# main_board.net
KiCad netlist of a schematic drawn in EAGLE
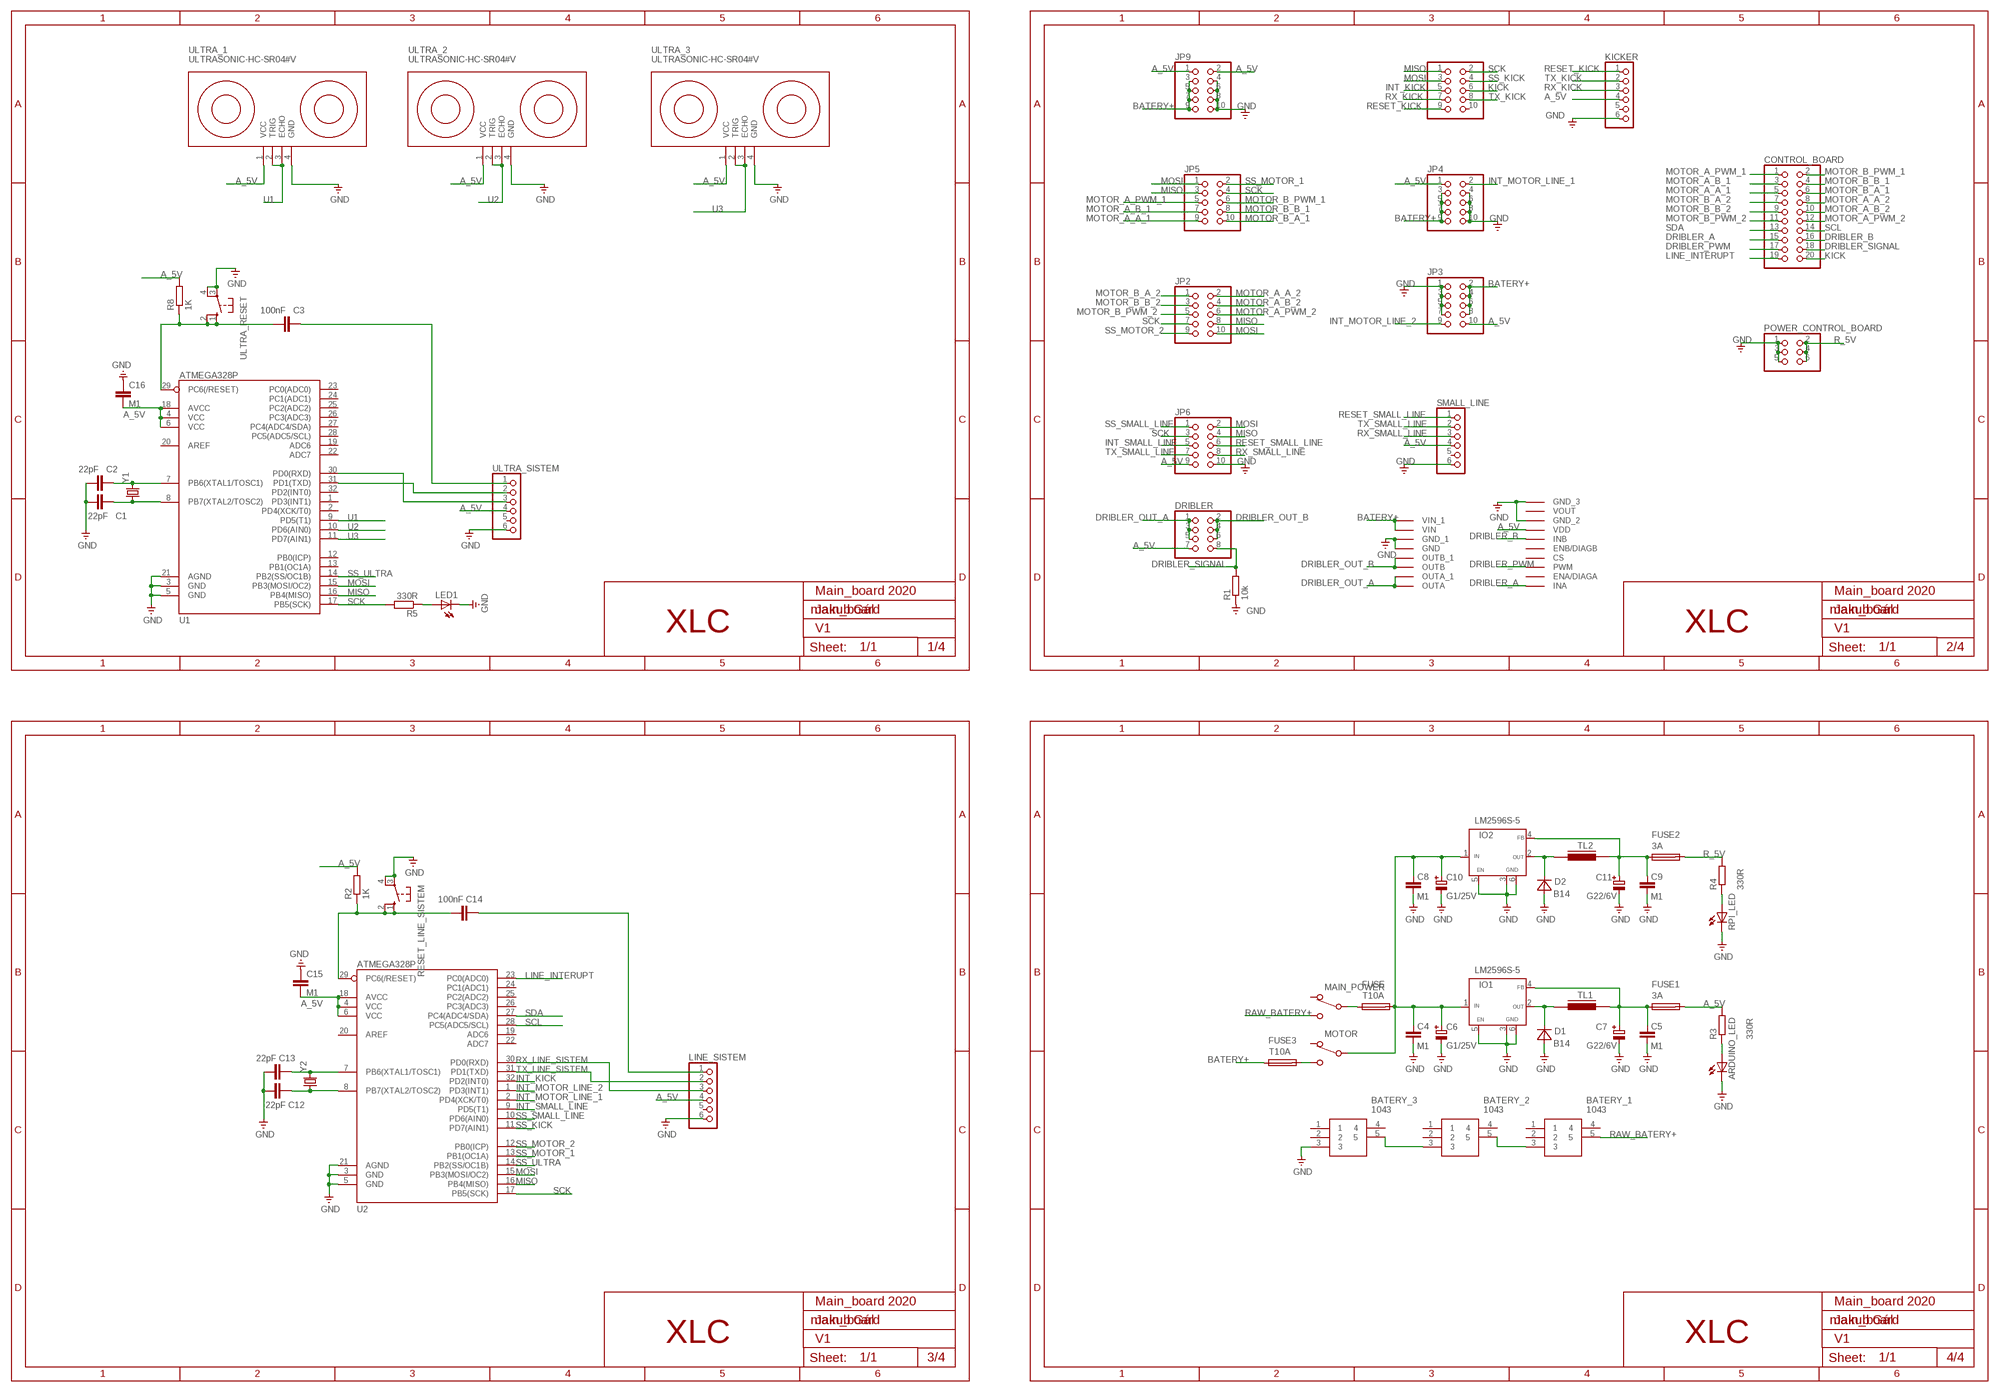
[diagram p0: schematic, sheet 1]

(export (version "E")
  (design (tool "Eeschema 10.0.6"))
  (components
    (comp (ref "ARDUINO_LED")
      (value "LEDCHIPLED_0603")
      (footprint "eagle-import:CHIPLED_0603")
      (libsource (lib "eagle-import") (part "LEDCHIPLED_0603"))
    )
    (comp (ref "BATERY_1")
      (value "1043")
      (footprint "eagle-import:1043")
      (fields (field (name "MOUSER_PART_NUMBER") "534-1043"))
      (libsource (lib "eagle-import") (part "1043"))
    )
    (comp (ref "BATERY_2")
      (value "1043")
      (footprint "eagle-import:1043")
      (fields (field (name "MOUSER_PART_NUMBER") "534-1043"))
      (libsource (lib "eagle-import") (part "1043"))
    )
    (comp (ref "BATERY_3")
      (value "1043")
      (footprint "eagle-import:1043")
      (fields (field (name "MOUSER_PART_NUMBER") "534-1043"))
      (libsource (lib "eagle-import") (part "1043"))
    )
    (comp (ref "C1")
      (value "22pF")
      (footprint "eagle-import:C0603")
      (libsource (lib "eagle-import") (part "C-EUC0603"))
    )
    (comp (ref "C2")
      (value "22pF")
      (footprint "eagle-import:C0603")
      (libsource (lib "eagle-import") (part "C-EUC0603"))
    )
    (comp (ref "C3")
      (value "100nF")
      (footprint "eagle-import:C0603")
      (libsource (lib "eagle-import") (part "C-EUC0603"))
    )
    (comp (ref "C4")
      (value "M1")
      (footprint "eagle-import:SMD-1206")
      (libsource (lib "eagle-import") (part "KOND-KERAM1206-SMD"))
    )
    (comp (ref "C5")
      (value "M1")
      (footprint "eagle-import:SMD-1206")
      (libsource (lib "eagle-import") (part "KOND-KERAM1206-SMD"))
    )
    (comp (ref "C6")
      (value "G1/25V")
      (footprint "eagle-import:SMD-ELE-D")
      (libsource (lib "eagle-import") (part "KOND-ELEKTD-SMD"))
    )
    (comp (ref "C7")
      (value "G22/6V")
      (footprint "eagle-import:SMD-ELE-D")
      (libsource (lib "eagle-import") (part "KOND-ELEKTD-SMD"))
    )
    (comp (ref "C8")
      (value "M1")
      (footprint "eagle-import:SMD-1206")
      (libsource (lib "eagle-import") (part "KOND-KERAM1206-SMD"))
    )
    (comp (ref "C9")
      (value "M1")
      (footprint "eagle-import:SMD-1206")
      (libsource (lib "eagle-import") (part "KOND-KERAM1206-SMD"))
    )
    (comp (ref "C10")
      (value "G1/25V")
      (footprint "eagle-import:SMD-ELE-D")
      (libsource (lib "eagle-import") (part "KOND-ELEKTD-SMD"))
    )
    (comp (ref "C11")
      (value "G22/6V")
      (footprint "eagle-import:SMD-ELE-D")
      (libsource (lib "eagle-import") (part "KOND-ELEKTD-SMD"))
    )
    (comp (ref "C12")
      (value "22pF")
      (footprint "eagle-import:C0603")
      (libsource (lib "eagle-import") (part "C-EUC0603"))
    )
    (comp (ref "C13")
      (value "22pF")
      (footprint "eagle-import:C0603")
      (libsource (lib "eagle-import") (part "C-EUC0603"))
    )
    (comp (ref "C14")
      (value "100nF")
      (footprint "eagle-import:C0603")
      (libsource (lib "eagle-import") (part "C-EUC0603"))
    )
    (comp (ref "C15")
      (value "M1")
      (footprint "eagle-import:C0603")
      (libsource (lib "eagle-import") (part "rcl_334_C-EUC0603"))
    )
    (comp (ref "C16")
      (value "M1")
      (footprint "eagle-import:C0603")
      (libsource (lib "eagle-import") (part "rcl_334_C-EUC0603"))
    )
    (comp (ref "CONTROL_BOARD")
      (value "PINHD-2X10_2.54-SMD")
      (footprint "eagle-import:2X10SMD")
      (libsource (lib "eagle-import") (part "PINHD-2X10_2.54-SMD"))
    )
    (comp (ref "D1")
      (value "B14")
      (footprint "eagle-import:D-3,6X5,5")
      (libsource (lib "eagle-import") (part "DIODASMD-3,6X5,5"))
    )
    (comp (ref "D2")
      (value "B14")
      (footprint "eagle-import:D-3,6X5,5")
      (libsource (lib "eagle-import") (part "DIODASMD-3,6X5,5"))
    )
    (comp (ref "DRIBLER")
      (value "PINHD-2X4_2.54-SMD")
      (footprint "eagle-import:2X04SMD")
      (libsource (lib "eagle-import") (part "PINHD-2X4_2.54-SMD"))
    )
    (comp (ref "FUSE")
      (value "T10A")
      (footprint "eagle-import:SH22,5A")
      (libsource (lib "eagle-import") (part "POISTKA2A"))
    )
    (comp (ref "FUSE1")
      (value "3A")
      (footprint "eagle-import:SH22,5A")
      (libsource (lib "eagle-import") (part "POISTKA2A"))
    )
    (comp (ref "FUSE2")
      (value "3A")
      (footprint "eagle-import:SH22,5A")
      (libsource (lib "eagle-import") (part "POISTKA2A"))
    )
    (comp (ref "FUSE3")
      (value "T10A")
      (footprint "eagle-import:SH22,5A")
      (libsource (lib "eagle-import") (part "POISTKA2A"))
    )
    (comp (ref "IO1")
      (value "LM2596S-5")
      (footprint "eagle-import:TO263-5")
      (libsource (lib "eagle-import") (part "LM2596S"))
    )
    (comp (ref "IO2")
      (value "LM2596S-5")
      (footprint "eagle-import:TO263-5")
      (libsource (lib "eagle-import") (part "LM2596S"))
    )
    (comp (ref "JP2")
      (value "PINHD-2X5_2.54-SMD")
      (footprint "eagle-import:2X05SMD")
      (libsource (lib "eagle-import") (part "PINHD-2X5_2.54-SMD"))
    )
    (comp (ref "JP3")
      (value "PINHD-2X5_2.54-SMD")
      (footprint "eagle-import:2X05SMD")
      (libsource (lib "eagle-import") (part "PINHD-2X5_2.54-SMD"))
    )
    (comp (ref "JP4")
      (value "PINHD-2X5_2.54-SMD")
      (footprint "eagle-import:2X05SMD")
      (libsource (lib "eagle-import") (part "PINHD-2X5_2.54-SMD"))
    )
    (comp (ref "JP5")
      (value "PINHD-2X5_2.54-SMD")
      (footprint "eagle-import:2X05SMD")
      (libsource (lib "eagle-import") (part "PINHD-2X5_2.54-SMD"))
    )
    (comp (ref "JP6")
      (value "PINHD-2X5_2.54-SMD")
      (footprint "eagle-import:2X05SMD")
      (libsource (lib "eagle-import") (part "PINHD-2X5_2.54-SMD"))
    )
    (comp (ref "JP8")
      (value "PINHD-2X5_2.54-SMD")
      (footprint "eagle-import:2X05SMD")
      (libsource (lib "eagle-import") (part "PINHD-2X5_2.54-SMD"))
    )
    (comp (ref "JP9")
      (value "PINHD-2X5_2.54-SMD")
      (footprint "eagle-import:2X05SMD")
      (libsource (lib "eagle-import") (part "PINHD-2X5_2.54-SMD"))
    )
    (comp (ref "KICKER")
      (value "PINHD-1X6")
      (footprint "eagle-import:1X06")
      (libsource (lib "eagle-import") (part "PINHD-1X6"))
    )
    (comp (ref "LED1")
      (value "LEDCHIPLED_0603")
      (footprint "eagle-import:CHIPLED_0603")
      (libsource (lib "eagle-import") (part "LEDCHIPLED_0603"))
    )
    (comp (ref "LINE_SISTEM")
      (value "PINHD-1X6")
      (footprint "eagle-import:1X06")
      (libsource (lib "eagle-import") (part "PINHD-1X6"))
    )
    (comp (ref "MAIN_POWER")
      (value "PREP-1PB")
      (footprint "eagle-import:P-B069B")
      (libsource (lib "eagle-import") (part "PREP-1PB"))
    )
    (comp (ref "MOTOR")
      (value "PREP-1PB")
      (footprint "eagle-import:P-B069B")
      (libsource (lib "eagle-import") (part "PREP-1PB"))
    )
    (comp (ref "POWER_CONTROL_BOARD")
      (value "PINHD-2X3_2.54-SMD")
      (footprint "eagle-import:2X03SMD")
      (libsource (lib "eagle-import") (part "PINHD-2X3_2.54-SMD"))
    )
    (comp (ref "R1")
      (value "10k")
      (footprint "eagle-import:R0603")
      (libsource (lib "eagle-import") (part "R-EU_R0603"))
    )
    (comp (ref "R2")
      (value "1K")
      (footprint "eagle-import:R0603")
      (libsource (lib "eagle-import") (part "R-EU_R0603"))
    )
    (comp (ref "R3")
      (value "330R")
      (footprint "eagle-import:R0603")
      (libsource (lib "eagle-import") (part "R-EU_R0603"))
    )
    (comp (ref "R4")
      (value "330R")
      (footprint "eagle-import:R0603")
      (libsource (lib "eagle-import") (part "R-EU_R0603"))
    )
    (comp (ref "R5")
      (value "330R")
      (footprint "eagle-import:R0603")
      (libsource (lib "eagle-import") (part "R-EU_R0603"))
    )
    (comp (ref "R8")
      (value "1K")
      (footprint "eagle-import:R0603")
      (libsource (lib "eagle-import") (part "R-EU_R0603"))
    )
    (comp (ref "RESET_LINE_SISTEM")
      (value "10-XX")
      (footprint "eagle-import:B3F-10XX")
      (fields (field (name "MPN") "B3F-1000"))
      (libsource (lib "eagle-import") (part "10-XX"))
    )
    (comp (ref "RPI_LED")
      (value "LEDCHIPLED_0603")
      (footprint "eagle-import:CHIPLED_0603")
      (libsource (lib "eagle-import") (part "LEDCHIPLED_0603"))
    )
    (comp (ref "SMALL_LINE")
      (value "PINHD-1X6")
      (footprint "eagle-import:1X06")
      (libsource (lib "eagle-import") (part "PINHD-1X6"))
    )
    (comp (ref "TL1")
      (value "INDUK-TLSMD1")
      (footprint "eagle-import:INDUK-TL")
      (libsource (lib "eagle-import") (part "INDUK-TLSMD1"))
    )
    (comp (ref "TL2")
      (value "INDUK-TLSMD1")
      (footprint "eagle-import:INDUK-TL")
      (libsource (lib "eagle-import") (part "INDUK-TLSMD1"))
    )
    (comp (ref "U$4")
      (value "MOTOR_DRIVER")
      (footprint "eagle-import:MOTOR_DRIVER")
      (libsource (lib "eagle-import") (part "MOTOR_DRIVER"))
    )
    (comp (ref "U1")
      (value "ATMEGA328P")
      (footprint "eagle-import:TQFP32-08")
      (libsource (lib "eagle-import") (part "ATMEGA328_SMT"))
    )
    (comp (ref "U2")
      (value "ATMEGA328P")
      (footprint "eagle-import:TQFP32-08")
      (libsource (lib "eagle-import") (part "ATMEGA328_SMT"))
    )
    (comp (ref "ULTRA_1")
      (value "ULTRASONIC-HC-SR04#V")
      (footprint "eagle-import:ULTRASONIC-HC-SR04#V")
      (libsource (lib "eagle-import") (part "ULTRASONIC-HC-SR04#V"))
    )
    (comp (ref "ULTRA_2")
      (value "ULTRASONIC-HC-SR04#V")
      (footprint "eagle-import:ULTRASONIC-HC-SR04#V")
      (libsource (lib "eagle-import") (part "ULTRASONIC-HC-SR04#V"))
    )
    (comp (ref "ULTRA_3")
      (value "ULTRASONIC-HC-SR04#V")
      (footprint "eagle-import:ULTRASONIC-HC-SR04#V")
      (libsource (lib "eagle-import") (part "ULTRASONIC-HC-SR04#V"))
    )
    (comp (ref "ULTRA_RESET")
      (value "10-XX")
      (footprint "eagle-import:B3F-10XX")
      (fields (field (name "MPN") "B3F-1000"))
      (libsource (lib "eagle-import") (part "10-XX"))
    )
    (comp (ref "ULTRA_SISTEM")
      (value "PINHD-1X6")
      (footprint "eagle-import:1X06")
      (libsource (lib "eagle-import") (part "PINHD-1X6"))
    )
    (comp (ref "Y1")
      (value "CRYSTALHC49US")
      (footprint "eagle-import:HC49US")
      (libsource (lib "eagle-import") (part "CRYSTALHC49US"))
    )
    (comp (ref "Y2")
      (value "CRYSTALHC49US")
      (footprint "eagle-import:HC49US")
      (libsource (lib "eagle-import") (part "CRYSTALHC49US"))
    )
  )
  (nets
    (net (code "1") (name "/A_5V") (class "Default")
      (node (ref "C15") (pin "2") (pinfunction "2_2") (pintype "passive"))
      (node (ref "C16") (pin "2") (pinfunction "2_2") (pintype "passive"))
      (node (ref "DRIBLER") (pin "7") (pinfunction "7_7") (pintype "passive"))
      (node (ref "FUSE1") (pin "2") (pinfunction "2_2") (pintype "passive"))
      (node (ref "JP3") (pin "10") (pinfunction "10_10") (pintype "passive"))
      (node (ref "JP4") (pin "1") (pinfunction "1_1") (pintype "passive"))
      (node (ref "JP6") (pin "9") (pinfunction "9_9") (pintype "passive"))
      (node (ref "JP9") (pin "1") (pinfunction "1_1") (pintype "passive"))
      (node (ref "JP9") (pin "2") (pinfunction "2_2") (pintype "passive"))
      (node (ref "KICKER") (pin "4") (pinfunction "4_4") (pintype "passive"))
      (node (ref "LINE_SISTEM") (pin "4") (pinfunction "4_4") (pintype "passive"))
      (node (ref "R2") (pin "2") (pinfunction "2_2") (pintype "passive"))
      (node (ref "R3") (pin "2") (pinfunction "2_2") (pintype "passive"))
      (node (ref "R8") (pin "2") (pinfunction "2_2") (pintype "passive"))
      (node (ref "SMALL_LINE") (pin "4") (pinfunction "4_4") (pintype "passive"))
      (node (ref "U$4") (pin "VDD") (pinfunction "VDD_VDD") (pintype "bidirectional"))
      (node (ref "U1") (pin "18") (pinfunction "AVCC_18") (pintype "bidirectional"))
      (node (ref "U1") (pin "4") (pinfunction "VCC_4") (pintype "bidirectional"))
      (node (ref "U1") (pin "6") (pinfunction "VCC_6") (pintype "bidirectional"))
      (node (ref "U2") (pin "18") (pinfunction "AVCC_18") (pintype "bidirectional"))
      (node (ref "U2") (pin "4") (pinfunction "VCC_4") (pintype "bidirectional"))
      (node (ref "U2") (pin "6") (pinfunction "VCC_6") (pintype "bidirectional"))
      (node (ref "ULTRA_1") (pin "1") (pinfunction "VCC_1") (pintype "power_in"))
      (node (ref "ULTRA_2") (pin "1") (pinfunction "VCC_1") (pintype "power_in"))
      (node (ref "ULTRA_3") (pin "1") (pinfunction "VCC_1") (pintype "power_in"))
      (node (ref "ULTRA_SISTEM") (pin "4") (pinfunction "4_4") (pintype "passive"))
    )
    (net (code "2") (name "/BATERY+") (class "Default")
      (node (ref "FUSE3") (pin "1") (pinfunction "1_1") (pintype "passive"))
      (node (ref "JP3") (pin "2") (pinfunction "2_2") (pintype "passive"))
      (node (ref "JP3") (pin "4") (pinfunction "4_4") (pintype "passive"))
      (node (ref "JP3") (pin "6") (pinfunction "6_6") (pintype "passive"))
      (node (ref "JP3") (pin "8") (pinfunction "8_8") (pintype "passive"))
      (node (ref "JP4") (pin "3") (pinfunction "3_3") (pintype "passive"))
      (node (ref "JP4") (pin "5") (pinfunction "5_5") (pintype "passive"))
      (node (ref "JP4") (pin "7") (pinfunction "7_7") (pintype "passive"))
      (node (ref "JP4") (pin "9") (pinfunction "9_9") (pintype "passive"))
      (node (ref "JP9") (pin "3") (pinfunction "3_3") (pintype "passive"))
      (node (ref "JP9") (pin "5") (pinfunction "5_5") (pintype "passive"))
      (node (ref "JP9") (pin "7") (pinfunction "7_7") (pintype "passive"))
      (node (ref "JP9") (pin "9") (pinfunction "9_9") (pintype "passive"))
      (node (ref "U$4") (pin "VIN") (pinfunction "VIN_VIN") (pintype "bidirectional"))
      (node (ref "U$4") (pin "VIN_1") (pinfunction "VIN_1_VIN_1") (pintype "bidirectional"))
    )
    (net (code "3") (name "/DRIBLER_A") (class "Default")
      (node (ref "CONTROL_BOARD") (pin "15") (pinfunction "15_15") (pintype "passive"))
      (node (ref "U$4") (pin "INA") (pinfunction "INA_INA") (pintype "bidirectional"))
    )
    (net (code "4") (name "/DRIBLER_B") (class "Default")
      (node (ref "CONTROL_BOARD") (pin "16") (pinfunction "16_16") (pintype "passive"))
      (node (ref "U$4") (pin "INB") (pinfunction "INB_INB") (pintype "bidirectional"))
    )
    (net (code "5") (name "/DRIBLER_OUT_A") (class "Default")
      (node (ref "DRIBLER") (pin "1") (pinfunction "1_1") (pintype "passive"))
      (node (ref "DRIBLER") (pin "3") (pinfunction "3_3") (pintype "passive"))
      (node (ref "DRIBLER") (pin "5") (pinfunction "5_5") (pintype "passive"))
      (node (ref "U$4") (pin "OUTA") (pinfunction "OUTA_OUTA") (pintype "bidirectional"))
      (node (ref "U$4") (pin "OUTA_1") (pinfunction "OUTA_1_OUTA_1") (pintype "bidirectional"))
    )
    (net (code "6") (name "/DRIBLER_OUT_B") (class "Default")
      (node (ref "DRIBLER") (pin "2") (pinfunction "2_2") (pintype "passive"))
      (node (ref "DRIBLER") (pin "4") (pinfunction "4_4") (pintype "passive"))
      (node (ref "DRIBLER") (pin "6") (pinfunction "6_6") (pintype "passive"))
      (node (ref "U$4") (pin "OUTB") (pinfunction "OUTB_OUTB") (pintype "bidirectional"))
      (node (ref "U$4") (pin "OUTB_1") (pinfunction "OUTB_1_OUTB_1") (pintype "bidirectional"))
    )
    (net (code "7") (name "/DRIBLER_PWM") (class "Default")
      (node (ref "CONTROL_BOARD") (pin "17") (pinfunction "17_17") (pintype "passive"))
      (node (ref "U$4") (pin "PWM") (pinfunction "PWM_PWM") (pintype "bidirectional"))
    )
    (net (code "8") (name "/DRIBLER_SIGNAL") (class "Default")
      (node (ref "CONTROL_BOARD") (pin "18") (pinfunction "18_18") (pintype "passive"))
      (node (ref "DRIBLER") (pin "8") (pinfunction "8_8") (pintype "passive"))
      (node (ref "R1") (pin "2") (pinfunction "2_2") (pintype "passive"))
    )
    (net (code "9") (name "/INT_KICK") (class "Default")
      (node (ref "JP8") (pin "5") (pinfunction "5_5") (pintype "passive"))
      (node (ref "U2") (pin "32") (pinfunction "PD2(INT0)_32") (pintype "bidirectional"))
    )
    (net (code "10") (name "/INT_MOTOR_LINE_1") (class "Default")
      (node (ref "JP4") (pin "2") (pinfunction "2_2") (pintype "passive"))
      (node (ref "U2") (pin "2") (pinfunction "PD4(XCK/T0)_2") (pintype "bidirectional"))
    )
    (net (code "11") (name "/INT_MOTOR_LINE_2") (class "Default")
      (node (ref "JP3") (pin "9") (pinfunction "9_9") (pintype "passive"))
      (node (ref "U2") (pin "1") (pinfunction "PD3(INT1)_1") (pintype "bidirectional"))
    )
    (net (code "12") (name "/INT_SMALL_LINE") (class "Default")
      (node (ref "JP6") (pin "5") (pinfunction "5_5") (pintype "passive"))
      (node (ref "U2") (pin "9") (pinfunction "PD5(T1)_9") (pintype "bidirectional"))
    )
    (net (code "13") (name "/KICK") (class "Default")
      (node (ref "CONTROL_BOARD") (pin "20") (pinfunction "20_20") (pintype "passive"))
      (node (ref "JP8") (pin "6") (pinfunction "6_6") (pintype "passive"))
    )
    (net (code "14") (name "/LINE_INTERUPT") (class "Default")
      (node (ref "CONTROL_BOARD") (pin "19") (pinfunction "19_19") (pintype "passive"))
      (node (ref "U2") (pin "23") (pinfunction "PC0(ADC0)_23") (pintype "bidirectional"))
    )
    (net (code "15") (name "/MISO") (class "Default")
      (node (ref "JP2") (pin "8") (pinfunction "8_8") (pintype "passive"))
      (node (ref "JP5") (pin "3") (pinfunction "3_3") (pintype "passive"))
      (node (ref "JP6") (pin "4") (pinfunction "4_4") (pintype "passive"))
      (node (ref "JP8") (pin "1") (pinfunction "1_1") (pintype "passive"))
      (node (ref "U1") (pin "16") (pinfunction "PB4(MISO)_16") (pintype "bidirectional"))
      (node (ref "U2") (pin "16") (pinfunction "PB4(MISO)_16") (pintype "bidirectional"))
    )
    (net (code "16") (name "/MOSI") (class "Default")
      (node (ref "JP2") (pin "10") (pinfunction "10_10") (pintype "passive"))
      (node (ref "JP5") (pin "1") (pinfunction "1_1") (pintype "passive"))
      (node (ref "JP6") (pin "2") (pinfunction "2_2") (pintype "passive"))
      (node (ref "JP8") (pin "3") (pinfunction "3_3") (pintype "passive"))
      (node (ref "U1") (pin "15") (pinfunction "PB3(MOSI/OC2)_15") (pintype "bidirectional"))
      (node (ref "U2") (pin "15") (pinfunction "PB3(MOSI/OC2)_15") (pintype "bidirectional"))
    )
    (net (code "17") (name "/MOTOR_A_A_1") (class "Default")
      (node (ref "CONTROL_BOARD") (pin "5") (pinfunction "5_5") (pintype "passive"))
      (node (ref "JP5") (pin "9") (pinfunction "9_9") (pintype "passive"))
    )
    (net (code "18") (name "/MOTOR_A_A_2") (class "Default")
      (node (ref "CONTROL_BOARD") (pin "8") (pinfunction "8_8") (pintype "passive"))
      (node (ref "JP2") (pin "2") (pinfunction "2_2") (pintype "passive"))
    )
    (net (code "19") (name "/MOTOR_A_B_1") (class "Default")
      (node (ref "CONTROL_BOARD") (pin "3") (pinfunction "3_3") (pintype "passive"))
      (node (ref "JP5") (pin "7") (pinfunction "7_7") (pintype "passive"))
    )
    (net (code "20") (name "/MOTOR_A_B_2") (class "Default")
      (node (ref "CONTROL_BOARD") (pin "10") (pinfunction "10_10") (pintype "passive"))
      (node (ref "JP2") (pin "4") (pinfunction "4_4") (pintype "passive"))
    )
    (net (code "21") (name "/MOTOR_A_PWM_1") (class "Default")
      (node (ref "CONTROL_BOARD") (pin "1") (pinfunction "1_1") (pintype "passive"))
      (node (ref "JP5") (pin "5") (pinfunction "5_5") (pintype "passive"))
    )
    (net (code "22") (name "/MOTOR_A_PWM_2") (class "Default")
      (node (ref "CONTROL_BOARD") (pin "12") (pinfunction "12_12") (pintype "passive"))
      (node (ref "JP2") (pin "6") (pinfunction "6_6") (pintype "passive"))
    )
    (net (code "23") (name "/MOTOR_B_A_1") (class "Default")
      (node (ref "CONTROL_BOARD") (pin "6") (pinfunction "6_6") (pintype "passive"))
      (node (ref "JP5") (pin "10") (pinfunction "10_10") (pintype "passive"))
    )
    (net (code "24") (name "/MOTOR_B_A_2") (class "Default")
      (node (ref "CONTROL_BOARD") (pin "7") (pinfunction "7_7") (pintype "passive"))
      (node (ref "JP2") (pin "1") (pinfunction "1_1") (pintype "passive"))
    )
    (net (code "25") (name "/MOTOR_B_B_1") (class "Default")
      (node (ref "CONTROL_BOARD") (pin "4") (pinfunction "4_4") (pintype "passive"))
      (node (ref "JP5") (pin "8") (pinfunction "8_8") (pintype "passive"))
    )
    (net (code "26") (name "/MOTOR_B_B_2") (class "Default")
      (node (ref "CONTROL_BOARD") (pin "9") (pinfunction "9_9") (pintype "passive"))
      (node (ref "JP2") (pin "3") (pinfunction "3_3") (pintype "passive"))
    )
    (net (code "27") (name "/MOTOR_B_PWM_1") (class "Default")
      (node (ref "CONTROL_BOARD") (pin "2") (pinfunction "2_2") (pintype "passive"))
      (node (ref "JP5") (pin "6") (pinfunction "6_6") (pintype "passive"))
    )
    (net (code "28") (name "/MOTOR_B_PWM_2") (class "Default")
      (node (ref "CONTROL_BOARD") (pin "11") (pinfunction "11_11") (pintype "passive"))
      (node (ref "JP2") (pin "5") (pinfunction "5_5") (pintype "passive"))
    )
    (net (code "29") (name "/RAW_BATERY+") (class "Default")
      (node (ref "BATERY_1") (pin "5") (pinfunction "5_5") (pintype "bidirectional"))
      (node (ref "MAIN_POWER") (pin "1") (pinfunction "1-OFF_1") (pintype "passive"))
    )
    (net (code "30") (name "/RESET_KICK") (class "Default")
      (node (ref "JP8") (pin "9") (pinfunction "9_9") (pintype "passive"))
      (node (ref "KICKER") (pin "1") (pinfunction "1_1") (pintype "passive"))
    )
    (net (code "31") (name "/RESET_SMALL_LINE") (class "Default")
      (node (ref "JP6") (pin "6") (pinfunction "6_6") (pintype "passive"))
      (node (ref "SMALL_LINE") (pin "1") (pinfunction "1_1") (pintype "passive"))
    )
    (net (code "32") (name "/RX_KICK") (class "Default")
      (node (ref "JP8") (pin "7") (pinfunction "7_7") (pintype "passive"))
      (node (ref "KICKER") (pin "3") (pinfunction "3_3") (pintype "passive"))
    )
    (net (code "33") (name "/RX_LINE_SISTEM") (class "Default")
      (node (ref "LINE_SISTEM") (pin "3") (pinfunction "3_3") (pintype "passive"))
      (node (ref "U2") (pin "30") (pinfunction "PD0(RXD)_30") (pintype "bidirectional"))
    )
    (net (code "34") (name "/RX_SMALL_LINE") (class "Default")
      (node (ref "JP6") (pin "8") (pinfunction "8_8") (pintype "passive"))
      (node (ref "SMALL_LINE") (pin "3") (pinfunction "3_3") (pintype "passive"))
    )
    (net (code "35") (name "/R_5V") (class "Default")
      (node (ref "FUSE2") (pin "2") (pinfunction "2_2") (pintype "passive"))
      (node (ref "POWER_CONTROL_BOARD") (pin "2") (pinfunction "2_2") (pintype "passive"))
      (node (ref "POWER_CONTROL_BOARD") (pin "4") (pinfunction "4_4") (pintype "passive"))
      (node (ref "POWER_CONTROL_BOARD") (pin "6") (pinfunction "6_6") (pintype "passive"))
      (node (ref "R4") (pin "2") (pinfunction "2_2") (pintype "passive"))
    )
    (net (code "36") (name "/SCK") (class "Default")
      (node (ref "JP2") (pin "7") (pinfunction "7_7") (pintype "passive"))
      (node (ref "JP5") (pin "4") (pinfunction "4_4") (pintype "passive"))
      (node (ref "JP6") (pin "3") (pinfunction "3_3") (pintype "passive"))
      (node (ref "JP8") (pin "2") (pinfunction "2_2") (pintype "passive"))
      (node (ref "R5") (pin "2") (pinfunction "2_2") (pintype "passive"))
      (node (ref "U1") (pin "17") (pinfunction "PB5(SCK)_17") (pintype "bidirectional"))
      (node (ref "U2") (pin "17") (pinfunction "PB5(SCK)_17") (pintype "bidirectional"))
    )
    (net (code "37") (name "/SCL") (class "Default")
      (node (ref "CONTROL_BOARD") (pin "14") (pinfunction "14_14") (pintype "passive"))
      (node (ref "U2") (pin "28") (pinfunction "PC5(ADC5/SCL)_28") (pintype "bidirectional"))
    )
    (net (code "38") (name "/SDA") (class "Default")
      (node (ref "CONTROL_BOARD") (pin "13") (pinfunction "13_13") (pintype "passive"))
      (node (ref "U2") (pin "27") (pinfunction "PC4(ADC4/SDA)_27") (pintype "bidirectional"))
    )
    (net (code "39") (name "/SS_KICK") (class "Default")
      (node (ref "JP8") (pin "4") (pinfunction "4_4") (pintype "passive"))
      (node (ref "U2") (pin "11") (pinfunction "PD7(AIN1)_11") (pintype "bidirectional"))
    )
    (net (code "40") (name "/SS_MOTOR_1") (class "Default")
      (node (ref "JP5") (pin "2") (pinfunction "2_2") (pintype "passive"))
      (node (ref "U2") (pin "13") (pinfunction "PB1(OC1A)_13") (pintype "bidirectional"))
    )
    (net (code "41") (name "/SS_MOTOR_2") (class "Default")
      (node (ref "JP2") (pin "9") (pinfunction "9_9") (pintype "passive"))
      (node (ref "U2") (pin "12") (pinfunction "PB0(ICP)_12") (pintype "bidirectional"))
    )
    (net (code "42") (name "/SS_SMALL_LINE") (class "Default")
      (node (ref "JP6") (pin "1") (pinfunction "1_1") (pintype "passive"))
      (node (ref "U2") (pin "10") (pinfunction "PD6(AIN0)_10") (pintype "bidirectional"))
    )
    (net (code "43") (name "/SS_ULTRA") (class "Default")
      (node (ref "U1") (pin "14") (pinfunction "PB2(SS/OC1B)_14") (pintype "bidirectional"))
      (node (ref "U2") (pin "14") (pinfunction "PB2(SS/OC1B)_14") (pintype "bidirectional"))
    )
    (net (code "44") (name "/TX_KICK") (class "Default")
      (node (ref "JP8") (pin "8") (pinfunction "8_8") (pintype "passive"))
      (node (ref "KICKER") (pin "2") (pinfunction "2_2") (pintype "passive"))
    )
    (net (code "45") (name "/TX_LINE_SISTEM") (class "Default")
      (node (ref "LINE_SISTEM") (pin "2") (pinfunction "2_2") (pintype "passive"))
      (node (ref "U2") (pin "31") (pinfunction "PD1(TXD)_31") (pintype "bidirectional"))
    )
    (net (code "46") (name "/TX_SMALL_LINE") (class "Default")
      (node (ref "JP6") (pin "7") (pinfunction "7_7") (pintype "passive"))
      (node (ref "SMALL_LINE") (pin "2") (pinfunction "2_2") (pintype "passive"))
    )
    (net (code "47") (name "/U1") (class "Default")
      (node (ref "U1") (pin "9") (pinfunction "PD5(T1)_9") (pintype "bidirectional"))
      (node (ref "ULTRA_1") (pin "2") (pinfunction "TRIG_2") (pintype "input"))
      (node (ref "ULTRA_1") (pin "3") (pinfunction "ECHO_3") (pintype "output"))
    )
    (net (code "48") (name "/U2") (class "Default")
      (node (ref "U1") (pin "10") (pinfunction "PD6(AIN0)_10") (pintype "bidirectional"))
      (node (ref "ULTRA_2") (pin "2") (pinfunction "TRIG_2") (pintype "input"))
      (node (ref "ULTRA_2") (pin "3") (pinfunction "ECHO_3") (pintype "output"))
    )
    (net (code "49") (name "/U3") (class "Default")
      (node (ref "U1") (pin "11") (pinfunction "PD7(AIN1)_11") (pintype "bidirectional"))
      (node (ref "ULTRA_3") (pin "2") (pinfunction "TRIG_2") (pintype "input"))
      (node (ref "ULTRA_3") (pin "3") (pinfunction "ECHO_3") (pintype "output"))
    )
    (net (code "50") (name "GND") (class "Default")
      (node (ref "ARDUINO_LED") (pin "C") (pinfunction "C_C") (pintype "passive"))
      (node (ref "BATERY_3") (pin "3") (pinfunction "3_3") (pintype "bidirectional"))
      (node (ref "C1") (pin "1") (pinfunction "1_1") (pintype "passive"))
      (node (ref "C10") (pin "MINUS") (pinfunction "MINUS_MINUS") (pintype "passive"))
      (node (ref "C11") (pin "MINUS") (pinfunction "MINUS_MINUS") (pintype "passive"))
      (node (ref "C12") (pin "1") (pinfunction "1_1") (pintype "passive"))
      (node (ref "C13") (pin "1") (pinfunction "1_1") (pintype "passive"))
      (node (ref "C15") (pin "1") (pinfunction "1_1") (pintype "passive"))
      (node (ref "C16") (pin "1") (pinfunction "1_1") (pintype "passive"))
      (node (ref "C2") (pin "1") (pinfunction "1_1") (pintype "passive"))
      (node (ref "C4") (pin "1") (pinfunction "1_1") (pintype "passive"))
      (node (ref "C5") (pin "1") (pinfunction "1_1") (pintype "passive"))
      (node (ref "C6") (pin "MINUS") (pinfunction "MINUS_MINUS") (pintype "passive"))
      (node (ref "C7") (pin "MINUS") (pinfunction "MINUS_MINUS") (pintype "passive"))
      (node (ref "C8") (pin "1") (pinfunction "1_1") (pintype "passive"))
      (node (ref "C9") (pin "1") (pinfunction "1_1") (pintype "passive"))
      (node (ref "D1") (pin "A") (pinfunction "A_A") (pintype "passive"))
      (node (ref "D2") (pin "A") (pinfunction "A_A") (pintype "passive"))
      (node (ref "IO1") (pin "3") (pinfunction "GND_3") (pintype "power_in"))
      (node (ref "IO1") (pin "5") (pinfunction "EN_5") (pintype "input"))
      (node (ref "IO1") (pin "6") (pinfunction "GND_6") (pintype "power_in"))
      (node (ref "IO2") (pin "3") (pinfunction "GND_3") (pintype "power_in"))
      (node (ref "IO2") (pin "5") (pinfunction "EN_5") (pintype "input"))
      (node (ref "IO2") (pin "6") (pinfunction "GND_6") (pintype "power_in"))
      (node (ref "JP3") (pin "1") (pinfunction "1_1") (pintype "passive"))
      (node (ref "JP3") (pin "3") (pinfunction "3_3") (pintype "passive"))
      (node (ref "JP3") (pin "5") (pinfunction "5_5") (pintype "passive"))
      (node (ref "JP3") (pin "7") (pinfunction "7_7") (pintype "passive"))
      (node (ref "JP4") (pin "10") (pinfunction "10_10") (pintype "passive"))
      (node (ref "JP4") (pin "4") (pinfunction "4_4") (pintype "passive"))
      (node (ref "JP4") (pin "6") (pinfunction "6_6") (pintype "passive"))
      (node (ref "JP4") (pin "8") (pinfunction "8_8") (pintype "passive"))
      (node (ref "JP6") (pin "10") (pinfunction "10_10") (pintype "passive"))
      (node (ref "JP9") (pin "10") (pinfunction "10_10") (pintype "passive"))
      (node (ref "JP9") (pin "4") (pinfunction "4_4") (pintype "passive"))
      (node (ref "JP9") (pin "6") (pinfunction "6_6") (pintype "passive"))
      (node (ref "JP9") (pin "8") (pinfunction "8_8") (pintype "passive"))
      (node (ref "KICKER") (pin "6") (pinfunction "6_6") (pintype "passive"))
      (node (ref "LED1") (pin "C") (pinfunction "C_C") (pintype "passive"))
      (node (ref "LINE_SISTEM") (pin "6") (pinfunction "6_6") (pintype "passive"))
      (node (ref "POWER_CONTROL_BOARD") (pin "1") (pinfunction "1_1") (pintype "passive"))
      (node (ref "POWER_CONTROL_BOARD") (pin "3") (pinfunction "3_3") (pintype "passive"))
      (node (ref "POWER_CONTROL_BOARD") (pin "5") (pinfunction "5_5") (pintype "passive"))
      (node (ref "R1") (pin "1") (pinfunction "1_1") (pintype "passive"))
      (node (ref "RESET_LINE_SISTEM") (pin "3") (pinfunction "P_3") (pintype "passive"))
      (node (ref "RESET_LINE_SISTEM") (pin "4") (pinfunction "P1_4") (pintype "passive"))
      (node (ref "RPI_LED") (pin "C") (pinfunction "C_C") (pintype "passive"))
      (node (ref "SMALL_LINE") (pin "6") (pinfunction "6_6") (pintype "passive"))
      (node (ref "U$4") (pin "GND") (pinfunction "GND_GND") (pintype "bidirectional"))
      (node (ref "U$4") (pin "GND_1") (pinfunction "GND_1_GND_1") (pintype "bidirectional"))
      (node (ref "U$4") (pin "GND_2") (pinfunction "GND_2_GND_2") (pintype "bidirectional"))
      (node (ref "U$4") (pin "GND_3") (pinfunction "GND_3_GND_3") (pintype "bidirectional"))
      (node (ref "U1") (pin "21") (pinfunction "AGND_21") (pintype "bidirectional"))
      (node (ref "U1") (pin "3") (pinfunction "GND_3") (pintype "bidirectional"))
      (node (ref "U1") (pin "5") (pinfunction "GND_5") (pintype "bidirectional"))
      (node (ref "U2") (pin "21") (pinfunction "AGND_21") (pintype "bidirectional"))
      (node (ref "U2") (pin "3") (pinfunction "GND_3") (pintype "bidirectional"))
      (node (ref "U2") (pin "5") (pinfunction "GND_5") (pintype "bidirectional"))
      (node (ref "ULTRA_1") (pin "4") (pinfunction "GND_4") (pintype "power_in"))
      (node (ref "ULTRA_2") (pin "4") (pinfunction "GND_4") (pintype "power_in"))
      (node (ref "ULTRA_3") (pin "4") (pinfunction "GND_4") (pintype "power_in"))
      (node (ref "ULTRA_RESET") (pin "3") (pinfunction "P_3") (pintype "passive"))
      (node (ref "ULTRA_RESET") (pin "4") (pinfunction "P1_4") (pintype "passive"))
      (node (ref "ULTRA_SISTEM") (pin "6") (pinfunction "6_6") (pintype "passive"))
    )
    (net (code "51") (name "Net-(ARDUINO_LED-PadA)") (class "Default")
      (node (ref "ARDUINO_LED") (pin "A") (pinfunction "A_A") (pintype "passive"))
      (node (ref "R3") (pin "1") (pinfunction "1_1") (pintype "passive"))
    )
    (net (code "52") (name "Net-(BATERY_1-Pad3)") (class "Default")
      (node (ref "BATERY_1") (pin "3") (pinfunction "3_3") (pintype "bidirectional"))
      (node (ref "BATERY_2") (pin "5") (pinfunction "5_5") (pintype "bidirectional"))
    )
    (net (code "53") (name "Net-(BATERY_2-Pad3)") (class "Default")
      (node (ref "BATERY_2") (pin "3") (pinfunction "3_3") (pintype "bidirectional"))
      (node (ref "BATERY_3") (pin "5") (pinfunction "5_5") (pintype "bidirectional"))
    )
    (net (code "54") (name "Net-(C3-Pad2)") (class "Default")
      (node (ref "C3") (pin "2") (pinfunction "2_2") (pintype "passive"))
      (node (ref "ULTRA_SISTEM") (pin "1") (pinfunction "1_1") (pintype "passive"))
    )
    (net (code "55") (name "Net-(C14-Pad2)") (class "Default")
      (node (ref "C14") (pin "2") (pinfunction "2_2") (pintype "passive"))
      (node (ref "LINE_SISTEM") (pin "1") (pinfunction "1_1") (pintype "passive"))
    )
    (net (code "56") (name "Net-(IO1-FB)") (class "Default")
      (node (ref "C5") (pin "2") (pinfunction "2_2") (pintype "passive"))
      (node (ref "C7") (pin "PLUS") (pinfunction "PLUS_PLUS") (pintype "passive"))
      (node (ref "FUSE1") (pin "1") (pinfunction "1_1") (pintype "passive"))
      (node (ref "IO1") (pin "4") (pinfunction "FB_4") (pintype "input"))
      (node (ref "TL1") (pin "2") (pinfunction "2_2") (pintype "passive"))
    )
    (net (code "57") (name "Net-(IO1-IN)") (class "Default")
      (node (ref "C10") (pin "PLUS") (pinfunction "PLUS_PLUS") (pintype "passive"))
      (node (ref "C4") (pin "2") (pinfunction "2_2") (pintype "passive"))
      (node (ref "C6") (pin "PLUS") (pinfunction "PLUS_PLUS") (pintype "passive"))
      (node (ref "C8") (pin "2") (pinfunction "2_2") (pintype "passive"))
      (node (ref "FUSE") (pin "2") (pinfunction "2_2") (pintype "passive"))
      (node (ref "IO1") (pin "1") (pinfunction "IN_1") (pintype "input"))
      (node (ref "IO2") (pin "1") (pinfunction "IN_1") (pintype "input"))
      (node (ref "MOTOR") (pin "2") (pinfunction "2-COM_2") (pintype "passive"))
    )
    (net (code "58") (name "Net-(IO1-OUT)") (class "Default")
      (node (ref "D1") (pin "K") (pinfunction "K_K") (pintype "passive"))
      (node (ref "IO1") (pin "2") (pinfunction "OUT_2") (pintype "output"))
      (node (ref "TL1") (pin "1") (pinfunction "1_1") (pintype "passive"))
    )
    (net (code "59") (name "Net-(IO2-FB)") (class "Default")
      (node (ref "C11") (pin "PLUS") (pinfunction "PLUS_PLUS") (pintype "passive"))
      (node (ref "C9") (pin "2") (pinfunction "2_2") (pintype "passive"))
      (node (ref "FUSE2") (pin "1") (pinfunction "1_1") (pintype "passive"))
      (node (ref "IO2") (pin "4") (pinfunction "FB_4") (pintype "input"))
      (node (ref "TL2") (pin "2") (pinfunction "2_2") (pintype "passive"))
    )
    (net (code "60") (name "Net-(IO2-OUT)") (class "Default")
      (node (ref "D2") (pin "K") (pinfunction "K_K") (pintype "passive"))
      (node (ref "IO2") (pin "2") (pinfunction "OUT_2") (pintype "output"))
      (node (ref "TL2") (pin "1") (pinfunction "1_1") (pintype "passive"))
    )
    (net (code "61") (name "Net-(LED1-PadA)") (class "Default")
      (node (ref "LED1") (pin "A") (pinfunction "A_A") (pintype "passive"))
      (node (ref "R5") (pin "1") (pinfunction "1_1") (pintype "passive"))
    )
    (net (code "62") (name "Net-(MAIN_POWER-2-COM)") (class "Default")
      (node (ref "FUSE") (pin "1") (pinfunction "1_1") (pintype "passive"))
      (node (ref "MAIN_POWER") (pin "2") (pinfunction "2-COM_2") (pintype "passive"))
    )
    (net (code "63") (name "Net-(MOTOR-1-OFF)") (class "Default")
      (node (ref "FUSE3") (pin "2") (pinfunction "2_2") (pintype "passive"))
      (node (ref "MOTOR") (pin "1") (pinfunction "1-OFF_1") (pintype "passive"))
    )
    (net (code "64") (name "Net-(R4-Pad1)") (class "Default")
      (node (ref "R4") (pin "1") (pinfunction "1_1") (pintype "passive"))
      (node (ref "RPI_LED") (pin "A") (pinfunction "A_A") (pintype "passive"))
    )
    (net (code "65") (name "Net-(RESET_LINE_SISTEM-S)") (class "Default")
      (node (ref "C14") (pin "1") (pinfunction "1_1") (pintype "passive"))
      (node (ref "R2") (pin "1") (pinfunction "1_1") (pintype "passive"))
      (node (ref "RESET_LINE_SISTEM") (pin "1") (pinfunction "S_1") (pintype "passive"))
      (node (ref "RESET_LINE_SISTEM") (pin "2") (pinfunction "S1_2") (pintype "passive"))
      (node (ref "U2") (pin "29") (pinfunction "PC6(/RESET)_29") (pintype "bidirectional"))
    )
    (net (code "66") (name "Net-(U1-PB6(XTAL1{slash}TOSC1))") (class "Default")
      (node (ref "C2") (pin "2") (pinfunction "2_2") (pintype "passive"))
      (node (ref "U1") (pin "7") (pinfunction "PB6(XTAL1/TOSC1)_7") (pintype "bidirectional"))
      (node (ref "Y1") (pin "2") (pinfunction "2_2") (pintype "passive"))
    )
    (net (code "67") (name "Net-(U1-PB7(XTAL2{slash}TOSC2))") (class "Default")
      (node (ref "C1") (pin "2") (pinfunction "2_2") (pintype "passive"))
      (node (ref "U1") (pin "8") (pinfunction "PB7(XTAL2/TOSC2)_8") (pintype "bidirectional"))
      (node (ref "Y1") (pin "1") (pinfunction "1_1") (pintype "passive"))
    )
    (net (code "68") (name "Net-(U1-PC6({slash}RESET))") (class "Default")
      (node (ref "C3") (pin "1") (pinfunction "1_1") (pintype "passive"))
      (node (ref "R8") (pin "1") (pinfunction "1_1") (pintype "passive"))
      (node (ref "U1") (pin "29") (pinfunction "PC6(/RESET)_29") (pintype "bidirectional"))
      (node (ref "ULTRA_RESET") (pin "1") (pinfunction "S_1") (pintype "passive"))
      (node (ref "ULTRA_RESET") (pin "2") (pinfunction "S1_2") (pintype "passive"))
    )
    (net (code "69") (name "Net-(U1-PD0(RXD))") (class "Default")
      (node (ref "U1") (pin "30") (pinfunction "PD0(RXD)_30") (pintype "bidirectional"))
      (node (ref "ULTRA_SISTEM") (pin "3") (pinfunction "3_3") (pintype "passive"))
    )
    (net (code "70") (name "Net-(U1-PD1(TXD))") (class "Default")
      (node (ref "U1") (pin "31") (pinfunction "PD1(TXD)_31") (pintype "bidirectional"))
      (node (ref "ULTRA_SISTEM") (pin "2") (pinfunction "2_2") (pintype "passive"))
    )
    (net (code "71") (name "Net-(U2-PB6(XTAL1{slash}TOSC1))") (class "Default")
      (node (ref "C13") (pin "2") (pinfunction "2_2") (pintype "passive"))
      (node (ref "U2") (pin "7") (pinfunction "PB6(XTAL1/TOSC1)_7") (pintype "bidirectional"))
      (node (ref "Y2") (pin "2") (pinfunction "2_2") (pintype "passive"))
    )
    (net (code "72") (name "Net-(U2-PB7(XTAL2{slash}TOSC2))") (class "Default")
      (node (ref "C12") (pin "2") (pinfunction "2_2") (pintype "passive"))
      (node (ref "U2") (pin "8") (pinfunction "PB7(XTAL2/TOSC2)_8") (pintype "bidirectional"))
      (node (ref "Y2") (pin "1") (pinfunction "1_1") (pintype "passive"))
    )
    (net (code "73") (name "unconnected-(BATERY_1-Pad1)") (class "Default")
      (node (ref "BATERY_1") (pin "1") (pinfunction "1_1") (pintype "bidirectional"))
    )
    (net (code "74") (name "unconnected-(BATERY_1-Pad2)") (class "Default")
      (node (ref "BATERY_1") (pin "2") (pinfunction "2_2") (pintype "bidirectional"))
    )
    (net (code "75") (name "unconnected-(BATERY_1-Pad4)") (class "Default")
      (node (ref "BATERY_1") (pin "4") (pinfunction "4_4") (pintype "bidirectional"))
    )
    (net (code "76") (name "unconnected-(BATERY_2-Pad1)") (class "Default")
      (node (ref "BATERY_2") (pin "1") (pinfunction "1_1") (pintype "bidirectional"))
    )
    (net (code "77") (name "unconnected-(BATERY_2-Pad2)") (class "Default")
      (node (ref "BATERY_2") (pin "2") (pinfunction "2_2") (pintype "bidirectional"))
    )
    (net (code "78") (name "unconnected-(BATERY_2-Pad4)") (class "Default")
      (node (ref "BATERY_2") (pin "4") (pinfunction "4_4") (pintype "bidirectional"))
    )
    (net (code "79") (name "unconnected-(BATERY_3-Pad1)") (class "Default")
      (node (ref "BATERY_3") (pin "1") (pinfunction "1_1") (pintype "bidirectional"))
    )
    (net (code "80") (name "unconnected-(BATERY_3-Pad2)") (class "Default")
      (node (ref "BATERY_3") (pin "2") (pinfunction "2_2") (pintype "bidirectional"))
    )
    (net (code "81") (name "unconnected-(BATERY_3-Pad4)") (class "Default")
      (node (ref "BATERY_3") (pin "4") (pinfunction "4_4") (pintype "bidirectional"))
    )
    (net (code "82") (name "unconnected-(JP8-Pad10)") (class "Default")
      (node (ref "JP8") (pin "10") (pinfunction "10_10") (pintype "passive"))
    )
    (net (code "83") (name "unconnected-(KICKER-Pad5)") (class "Default")
      (node (ref "KICKER") (pin "5") (pinfunction "5_5") (pintype "passive"))
    )
    (net (code "84") (name "unconnected-(LINE_SISTEM-Pad5)") (class "Default")
      (node (ref "LINE_SISTEM") (pin "5") (pinfunction "5_5") (pintype "passive"))
    )
    (net (code "85") (name "unconnected-(MAIN_POWER-3-ON-Pad3)") (class "Default")
      (node (ref "MAIN_POWER") (pin "3") (pinfunction "3-ON_3") (pintype "passive"))
    )
    (net (code "86") (name "unconnected-(MOTOR-3-ON-Pad3)") (class "Default")
      (node (ref "MOTOR") (pin "3") (pinfunction "3-ON_3") (pintype "passive"))
    )
    (net (code "87") (name "unconnected-(SMALL_LINE-Pad5)") (class "Default")
      (node (ref "SMALL_LINE") (pin "5") (pinfunction "5_5") (pintype "passive"))
    )
    (net (code "88") (name "unconnected-(U$4-PadCS)") (class "Default")
      (node (ref "U$4") (pin "CS") (pinfunction "CS_CS") (pintype "bidirectional"))
    )
    (net (code "89") (name "unconnected-(U$4-PadENA{slash}DIAGA)") (class "Default")
      (node (ref "U$4") (pin "ENA/DIAGA") (pinfunction "ENA/DIAGA_ENA/DIAGA") (pintype "bidirectional"))
    )
    (net (code "90") (name "unconnected-(U$4-PadENB{slash}DIAGB)") (class "Default")
      (node (ref "U$4") (pin "ENB/DIAGB") (pinfunction "ENB/DIAGB_ENB/DIAGB") (pintype "bidirectional"))
    )
    (net (code "91") (name "unconnected-(U$4-PadVOUT)") (class "Default")
      (node (ref "U$4") (pin "VOUT") (pinfunction "VOUT_VOUT") (pintype "bidirectional"))
    )
    (net (code "92") (name "unconnected-(U1-ADC6-Pad19)") (class "Default")
      (node (ref "U1") (pin "19") (pinfunction "ADC6_19") (pintype "bidirectional"))
    )
    (net (code "93") (name "unconnected-(U1-ADC7-Pad22)") (class "Default")
      (node (ref "U1") (pin "22") (pinfunction "ADC7_22") (pintype "bidirectional"))
    )
    (net (code "94") (name "unconnected-(U1-AREF-Pad20)") (class "Default")
      (node (ref "U1") (pin "20") (pinfunction "AREF_20") (pintype "bidirectional"))
    )
    (net (code "95") (name "unconnected-(U1-PB0(ICP)-Pad12)") (class "Default")
      (node (ref "U1") (pin "12") (pinfunction "PB0(ICP)_12") (pintype "bidirectional"))
    )
    (net (code "96") (name "unconnected-(U1-PB1(OC1A)-Pad13)") (class "Default")
      (node (ref "U1") (pin "13") (pinfunction "PB1(OC1A)_13") (pintype "bidirectional"))
    )
    (net (code "97") (name "unconnected-(U1-PC0(ADC0)-Pad23)") (class "Default")
      (node (ref "U1") (pin "23") (pinfunction "PC0(ADC0)_23") (pintype "bidirectional"))
    )
    (net (code "98") (name "unconnected-(U1-PC1(ADC1)-Pad24)") (class "Default")
      (node (ref "U1") (pin "24") (pinfunction "PC1(ADC1)_24") (pintype "bidirectional"))
    )
    (net (code "99") (name "unconnected-(U1-PC2(ADC2)-Pad25)") (class "Default")
      (node (ref "U1") (pin "25") (pinfunction "PC2(ADC2)_25") (pintype "bidirectional"))
    )
    (net (code "100") (name "unconnected-(U1-PC3(ADC3)-Pad26)") (class "Default")
      (node (ref "U1") (pin "26") (pinfunction "PC3(ADC3)_26") (pintype "bidirectional"))
    )
    (net (code "101") (name "unconnected-(U1-PC4(ADC4{slash}SDA)-Pad27)") (class "Default")
      (node (ref "U1") (pin "27") (pinfunction "PC4(ADC4/SDA)_27") (pintype "bidirectional"))
    )
    (net (code "102") (name "unconnected-(U1-PC5(ADC5{slash}SCL)-Pad28)") (class "Default")
      (node (ref "U1") (pin "28") (pinfunction "PC5(ADC5/SCL)_28") (pintype "bidirectional"))
    )
    (net (code "103") (name "unconnected-(U1-PD2(INT0)-Pad32)") (class "Default")
      (node (ref "U1") (pin "32") (pinfunction "PD2(INT0)_32") (pintype "bidirectional"))
    )
    (net (code "104") (name "unconnected-(U1-PD3(INT1)-Pad1)") (class "Default")
      (node (ref "U1") (pin "1") (pinfunction "PD3(INT1)_1") (pintype "bidirectional"))
    )
    (net (code "105") (name "unconnected-(U1-PD4(XCK{slash}T0)-Pad2)") (class "Default")
      (node (ref "U1") (pin "2") (pinfunction "PD4(XCK/T0)_2") (pintype "bidirectional"))
    )
    (net (code "106") (name "unconnected-(U2-ADC6-Pad19)") (class "Default")
      (node (ref "U2") (pin "19") (pinfunction "ADC6_19") (pintype "bidirectional"))
    )
    (net (code "107") (name "unconnected-(U2-ADC7-Pad22)") (class "Default")
      (node (ref "U2") (pin "22") (pinfunction "ADC7_22") (pintype "bidirectional"))
    )
    (net (code "108") (name "unconnected-(U2-AREF-Pad20)") (class "Default")
      (node (ref "U2") (pin "20") (pinfunction "AREF_20") (pintype "bidirectional"))
    )
    (net (code "109") (name "unconnected-(U2-PC1(ADC1)-Pad24)") (class "Default")
      (node (ref "U2") (pin "24") (pinfunction "PC1(ADC1)_24") (pintype "bidirectional"))
    )
    (net (code "110") (name "unconnected-(U2-PC2(ADC2)-Pad25)") (class "Default")
      (node (ref "U2") (pin "25") (pinfunction "PC2(ADC2)_25") (pintype "bidirectional"))
    )
    (net (code "111") (name "unconnected-(U2-PC3(ADC3)-Pad26)") (class "Default")
      (node (ref "U2") (pin "26") (pinfunction "PC3(ADC3)_26") (pintype "bidirectional"))
    )
    (net (code "112") (name "unconnected-(ULTRA_SISTEM-Pad5)") (class "Default")
      (node (ref "ULTRA_SISTEM") (pin "5") (pinfunction "5_5") (pintype "passive"))
    )
  )
)
